# schematic_tsc.net
KiCad netlist of a schematic drawn in EAGLE
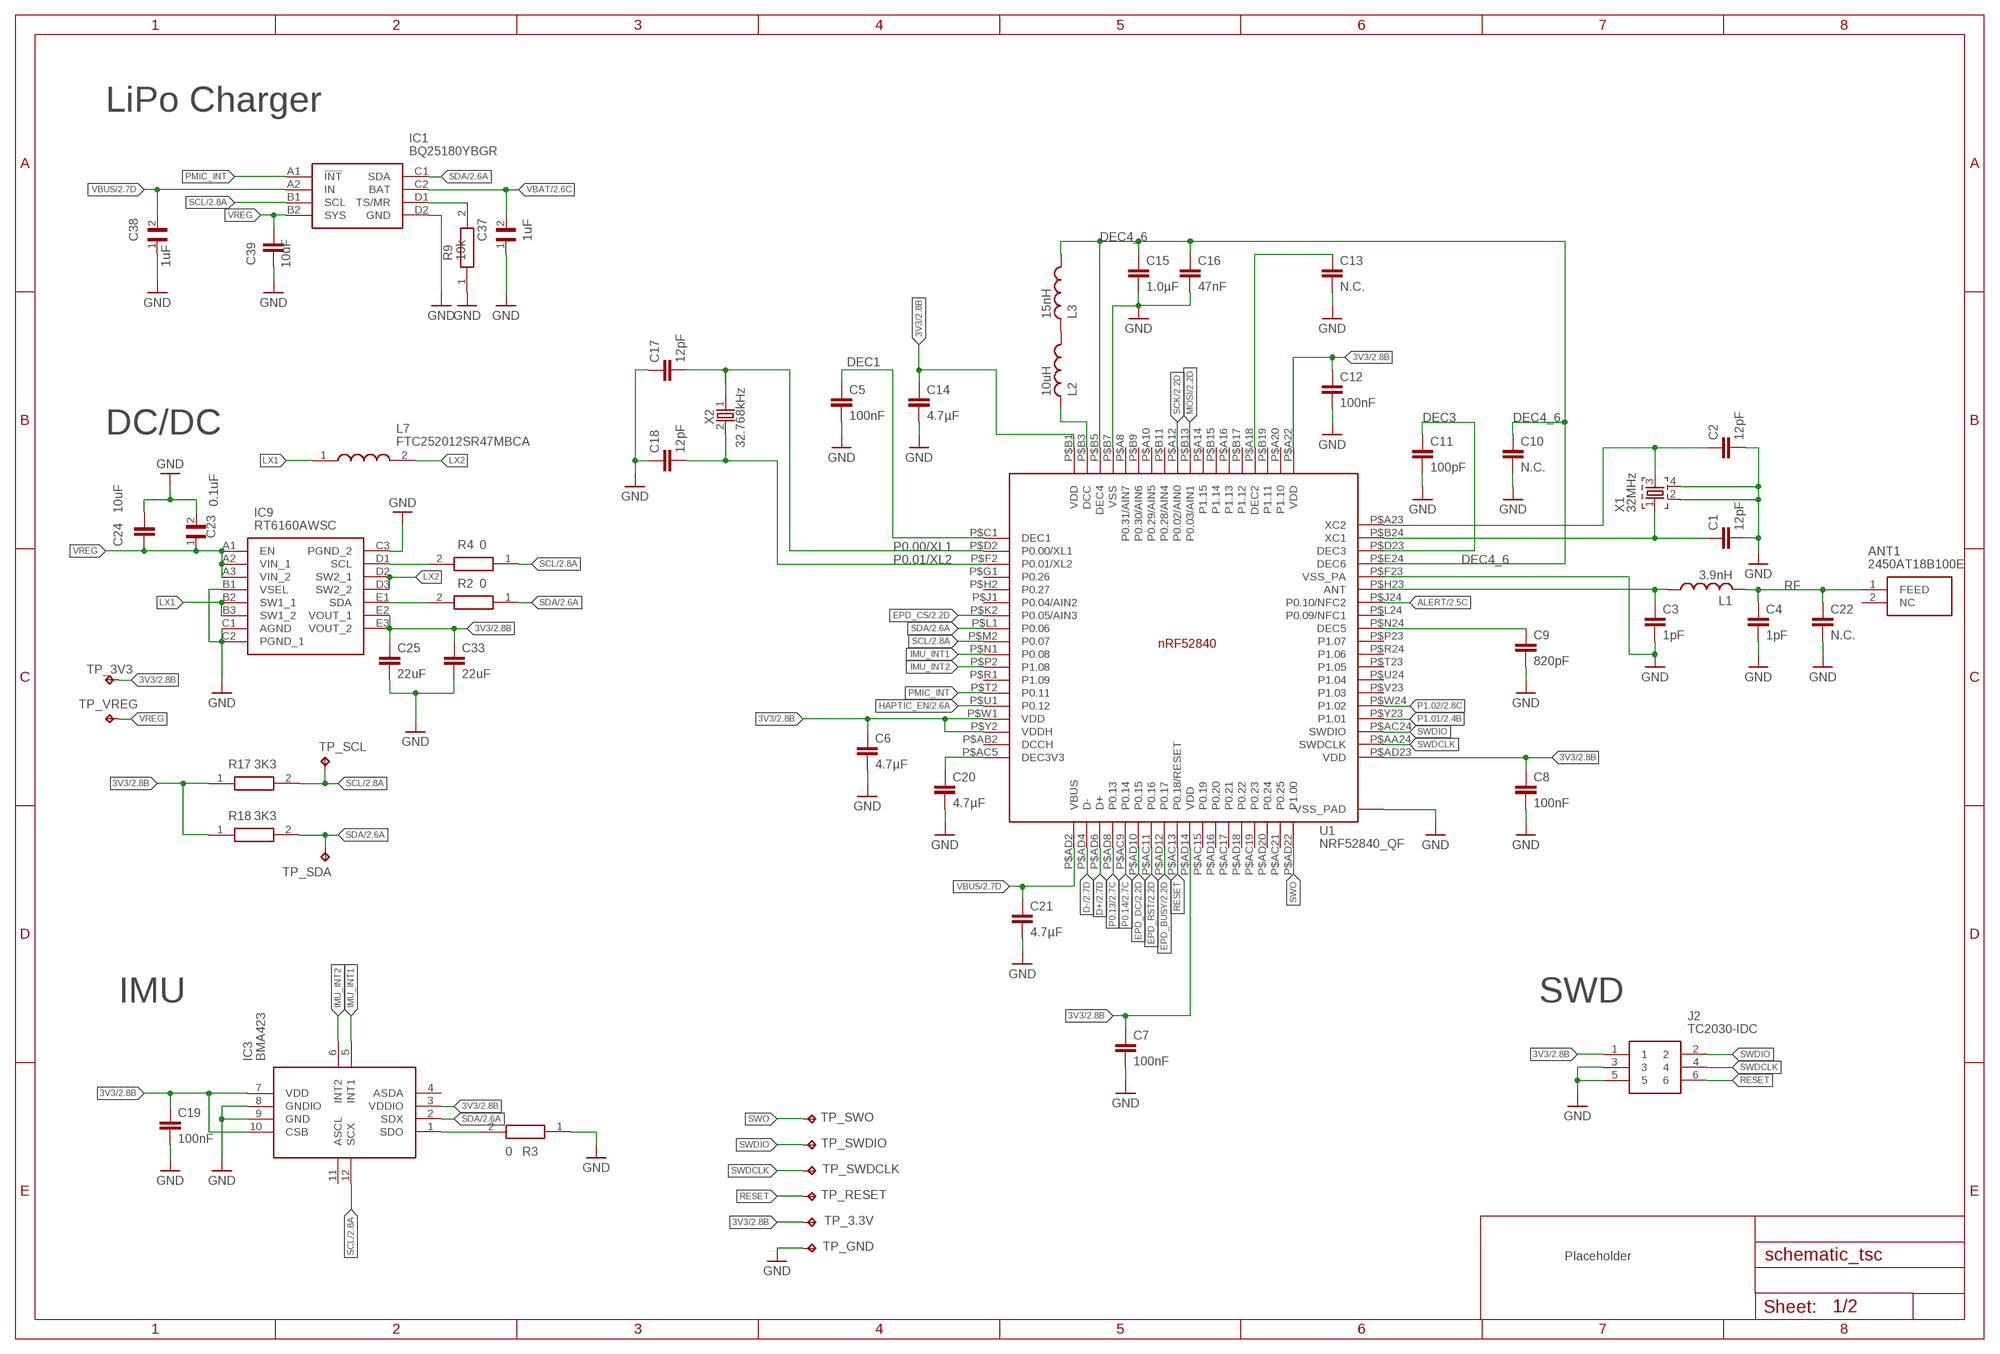
[diagram p0: schematic, sheet 1]
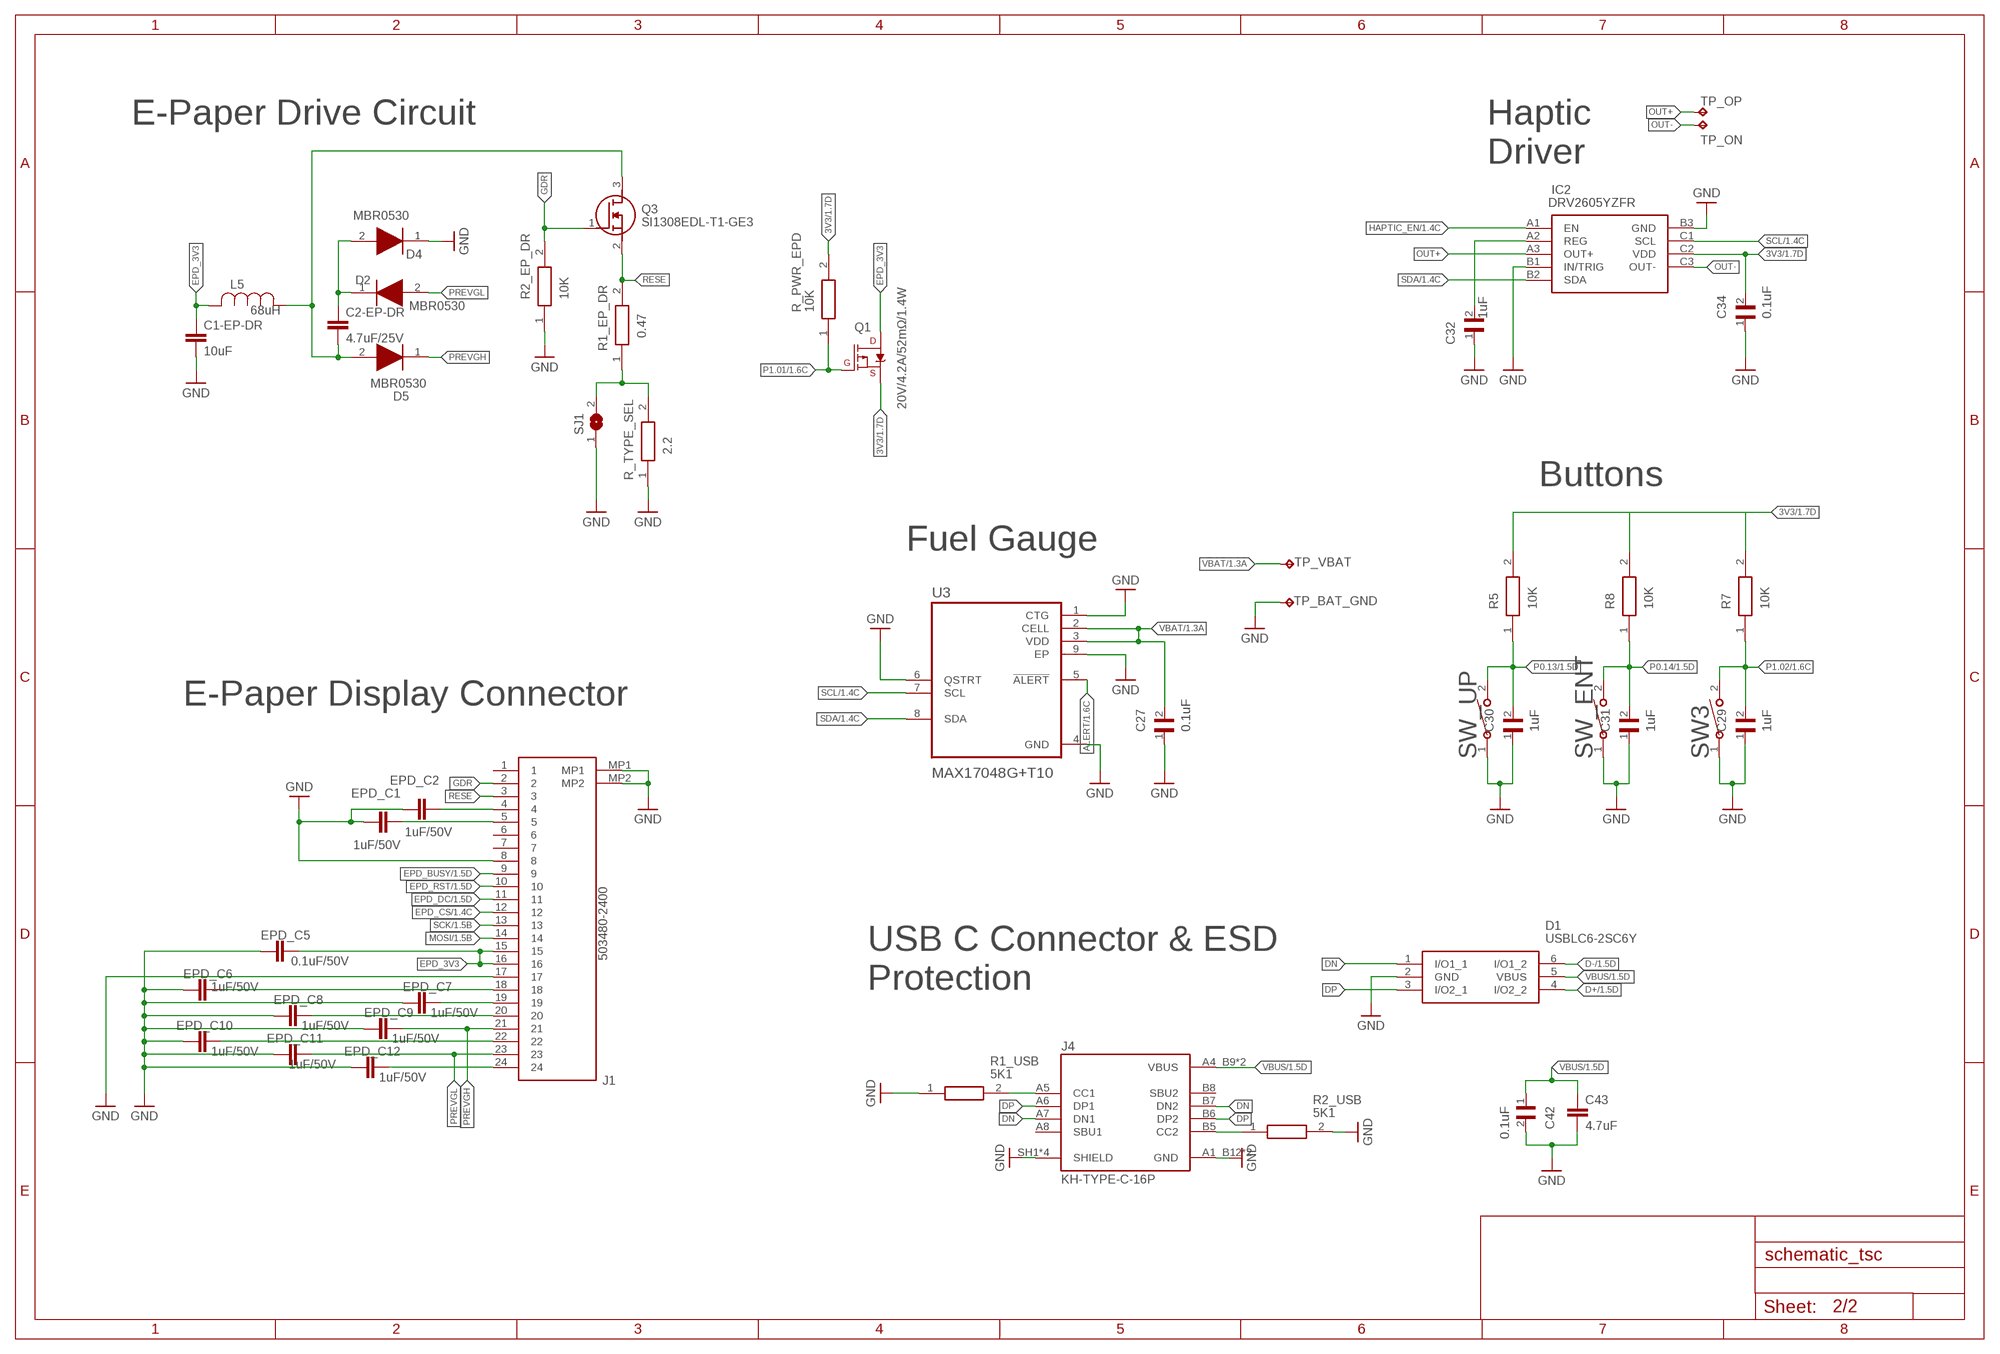
[diagram p1: schematic, sheet 2]

(export (version "E")
  (design (tool "Eeschema 10.0.6"))
  (components
    (comp (ref "ANT1")
      (value "2450AT18B100E")
      (footprint "eagle-import:2450AT18B100E_ANTC3216X140N")
      (fields (field (name "MOUSER_PART_NUMBER") "609-2450AT18B100E"))
      (libsource (lib "eagle-import") (part "2450AT18B100E_2450AT18B100E"))
    )
    (comp (ref "C1")
      (value "12pF")
      (footprint "eagle-import:NORDIC_NRF_3_RESC0201_L")
      (libsource (lib "eagle-import") (part "NORDIC_NRF_3_CAPACITOR_0201_L"))
    )
    (comp (ref "C2")
      (value "12pF")
      (footprint "eagle-import:NORDIC_NRF_3_RESC0201_L")
      (libsource (lib "eagle-import") (part "NORDIC_NRF_3_CAPACITOR_0201_L"))
    )
    (comp (ref "C3")
      (value "1pF")
      (footprint "eagle-import:NORDIC_NRF_3_RESC0201_L")
      (libsource (lib "eagle-import") (part "NORDIC_NRF_3_CAPACITOR_0201_L"))
    )
    (comp (ref "C4")
      (value "1pF")
      (footprint "eagle-import:NORDIC_NRF_3_RESC0201_L")
      (libsource (lib "eagle-import") (part "NORDIC_NRF_3_CAPACITOR_0201_L"))
    )
    (comp (ref "C5")
      (value "100nF")
      (footprint "eagle-import:NORDIC_NRF_3_RESC0201_L")
      (libsource (lib "eagle-import") (part "NORDIC_NRF_3_CAPACITOR_0201_L"))
    )
    (comp (ref "C6")
      (value "4.7µF")
      (footprint "eagle-import:NORDIC_NRF_3_RESC0402_L")
      (libsource (lib "eagle-import") (part "NORDIC_NRF_3_CAPACITOR_0402_L"))
    )
    (comp (ref "C7")
      (value "100nF")
      (footprint "eagle-import:NORDIC_NRF_3_RESC0201_L")
      (libsource (lib "eagle-import") (part "NORDIC_NRF_3_CAPACITOR_0201_L"))
    )
    (comp (ref "C8")
      (value "100nF")
      (footprint "eagle-import:NORDIC_NRF_3_RESC0201_L")
      (libsource (lib "eagle-import") (part "NORDIC_NRF_3_CAPACITOR_0201_L"))
    )
    (comp (ref "C9")
      (value "820pF")
      (footprint "eagle-import:NORDIC_NRF_3_RESC0201_L")
      (libsource (lib "eagle-import") (part "NORDIC_NRF_3_CAPACITOR_0201_L"))
    )
    (comp (ref "C10")
      (value "N.C.")
      (footprint "eagle-import:NORDIC_NRF_3_RESC0201_L")
      (libsource (lib "eagle-import") (part "NORDIC_NRF_3_CAPACITOR_0201_L"))
    )
    (comp (ref "C11")
      (value "100pF")
      (footprint "eagle-import:NORDIC_NRF_3_RESC0201_L")
      (libsource (lib "eagle-import") (part "NORDIC_NRF_3_CAPACITOR_0201_L"))
    )
    (comp (ref "C12")
      (value "100nF")
      (footprint "eagle-import:NORDIC_NRF_3_RESC0201_L")
      (libsource (lib "eagle-import") (part "NORDIC_NRF_3_CAPACITOR_0201_L"))
    )
    (comp (ref "C13")
      (value "N.C.")
      (footprint "eagle-import:NORDIC_NRF_3_RESC0201_L")
      (libsource (lib "eagle-import") (part "NORDIC_NRF_3_CAPACITOR_0201_L"))
    )
    (comp (ref "C14")
      (value "4.7µF")
      (footprint "eagle-import:NORDIC_NRF_3_RESC0402_L")
      (libsource (lib "eagle-import") (part "NORDIC_NRF_3_CAPACITOR_0402_L"))
    )
    (comp (ref "C15")
      (value "1.0µF")
      (footprint "eagle-import:NORDIC_NRF_3_RESC0402_L")
      (libsource (lib "eagle-import") (part "NORDIC_NRF_3_CAPACITOR_0402_L"))
    )
    (comp (ref "C16")
      (value "47nF")
      (footprint "eagle-import:NORDIC_NRF_3_RESC0201_L")
      (libsource (lib "eagle-import") (part "NORDIC_NRF_3_CAPACITOR_0201_L"))
    )
    (comp (ref "C17")
      (value "12pF")
      (footprint "eagle-import:NORDIC_NRF_3_RESC0201_L")
      (libsource (lib "eagle-import") (part "NORDIC_NRF_3_CAPACITOR_0201_L"))
    )
    (comp (ref "C18")
      (value "12pF")
      (footprint "eagle-import:NORDIC_NRF_3_RESC0201_L")
      (libsource (lib "eagle-import") (part "NORDIC_NRF_3_CAPACITOR_0201_L"))
    )
    (comp (ref "C19")
      (value "100nF")
      (footprint "eagle-import:NORDIC_NRF_3_RESC0201_L")
      (libsource (lib "eagle-import") (part "NORDIC_NRF_3_CAPACITOR_0201_L"))
    )
    (comp (ref "C20")
      (value "4.7µF")
      (footprint "eagle-import:NORDIC_NRF_3_RESC0402_L")
      (libsource (lib "eagle-import") (part "NORDIC_NRF_3_CAPACITOR_0402_L"))
    )
    (comp (ref "C21")
      (value "4.7µF")
      (footprint "eagle-import:NORDIC_NRF_3_RESC0402_L")
      (libsource (lib "eagle-import") (part "NORDIC_NRF_3_CAPACITOR_0402_L"))
    )
    (comp (ref "C22")
      (value "N.C.")
      (footprint "eagle-import:NORDIC_NRF_3_RESC0201_L")
      (libsource (lib "eagle-import") (part "NORDIC_NRF_3_CAPACITOR_0201_L"))
    )
    (comp (ref "C23")
      (value "0.1uF")
      (footprint "eagle-import:GRM011R60J152KE01L_2_CAPC0201X13N")
      (fields (field (name "MF") "Murata") (field (name "MP") "GRM011R60J152KE01L"))
      (libsource (lib "eagle-import") (part "GRM011R60J152KE01L_2_GRM011R60J152KE01L"))
    )
    (comp (ref "C24")
      (value "10uF")
      (footprint "eagle-import:NORDIC_NRF_3_RESC0402_L")
      (libsource (lib "eagle-import") (part "NORDIC_NRF_3_CAPACITOR_0402_L"))
    )
    (comp (ref "C25")
      (value "22uF")
      (footprint "eagle-import:NORDIC_NRF_3_RESC0402_L")
      (libsource (lib "eagle-import") (part "NORDIC_NRF_3_CAPACITOR_0402_L"))
    )
    (comp (ref "C33")
      (value "22uF")
      (footprint "eagle-import:NORDIC_NRF_3_RESC0402_L")
      (libsource (lib "eagle-import") (part "NORDIC_NRF_3_CAPACITOR_0402_L"))
    )
    (comp (ref "C37")
      (value "1uF")
      (footprint "eagle-import:GRM011R60J152KE01L_2_CAPC0201X13N")
      (fields (field (name "MF") "Murata") (field (name "MP") "GRM011R60J152KE01L"))
      (libsource (lib "eagle-import") (part "GRM011R60J152KE01L_2_GRM011R60J152KE01L"))
    )
    (comp (ref "C38")
      (value "1uF")
      (footprint "eagle-import:GRM011R60J152KE01L_2_CAPC0201X13N")
      (fields (field (name "MF") "Murata") (field (name "MP") "GRM011R60J152KE01L"))
      (libsource (lib "eagle-import") (part "GRM011R60J152KE01L_2_GRM011R60J152KE01L"))
    )
    (comp (ref "C39")
      (value "10uF")
      (footprint "eagle-import:NORDIC_NRF_3_RESC0402_L")
      (libsource (lib "eagle-import") (part "NORDIC_NRF_3_CAPACITOR_0402_L"))
    )
    (comp (ref "IC1")
      (value "BQ25180YBGR")
      (footprint "eagle-import:BQ25180YBGR_BGA8C40P2X4_100X155X50")
      (fields (field (name "MOUSER_PART_NUMBER") "595-BQ25180YBGR"))
      (libsource (lib "eagle-import") (part "BQ25180YBGR_BQ25180YBGR"))
    )
    (comp (ref "IC3")
      (value "BMA423")
      (footprint "eagle-import:BMA423_BMA423")
      (fields (field (name "MOUSER_PART_NUMBER") "262-BMA423"))
      (libsource (lib "eagle-import") (part "BMA423_BMA423"))
    )
    (comp (ref "IC9")
      (value "RT6160AWSC")
      (footprint "eagle-import:RT6160AWSC_BGA15C40P3X5_140X230X60")
      (fields (field (name "MOUSER_PART_NUMBER") "835-RT6160AWSC"))
      (libsource (lib "eagle-import") (part "RT6160AWSC_RT6160AWSC"))
    )
    (comp (ref "J2")
      (value "TC2030-IDC")
      (footprint "eagle-import:TC2030-IDC_TC2030IDC")
      (libsource (lib "eagle-import") (part "TC2030-IDC_TC2030-IDC"))
    )
    (comp (ref "L1")
      (value "3.9nH")
      (footprint "eagle-import:NORDIC_NRF_2_RESC0402_L")
      (libsource (lib "eagle-import") (part "NORDIC_NRF_2_INDUCTOR_0402_L"))
    )
    (comp (ref "L2")
      (value "10uH")
      (footprint "eagle-import:NORDIC_NRF_2_RESC0603_L")
      (libsource (lib "eagle-import") (part "NORDIC_NRF_2_INDUCTOR_0603_L"))
    )
    (comp (ref "L3")
      (value "15nH")
      (footprint "eagle-import:NORDIC_NRF_2_RESC0402_L")
      (libsource (lib "eagle-import") (part "NORDIC_NRF_2_INDUCTOR_0402_L"))
    )
    (comp (ref "L7")
      (value "FTC252012SR47MBCA")
      (footprint "eagle-import:MLP2016SR47MT0S1_INDC2016X100N")
      (libsource (lib "eagle-import") (part "MLP2016SR47MT0S1_FTC252012SR47MBCA"))
    )
    (comp (ref "R2")
      (value "0")
      (footprint "eagle-import:CPF0201D7K68C1_0201")
      (libsource (lib "eagle-import") (part "CPF0201D7K68C1_CPF0201D7K68C1"))
    )
    (comp (ref "R3")
      (value "0")
      (footprint "eagle-import:ERA-1AEB3401C_0201")
      (libsource (lib "eagle-import") (part "ERA-1AEB3401C_CPF0201D7K68C1"))
    )
    (comp (ref "R4")
      (value "0")
      (footprint "eagle-import:CPF0201D7K68C1_0201")
      (libsource (lib "eagle-import") (part "CPF0201D7K68C1_CPF0201D7K68C1"))
    )
    (comp (ref "R9")
      (value "10k")
      (footprint "eagle-import:CPF0201D7K68C1_0201")
      (libsource (lib "eagle-import") (part "CPF0201D7K68C1_CPF0201D7K68C1"))
    )
    (comp (ref "R17")
      (value "3K3")
      (footprint "eagle-import:ERA-1AEB3401C_0201")
      (libsource (lib "eagle-import") (part "ERA-1AEB3401C_CPF0201D7K68C1"))
    )
    (comp (ref "R18")
      (value "3K3")
      (footprint "eagle-import:ERA-1AEB3401C_0201")
      (libsource (lib "eagle-import") (part "ERA-1AEB3401C_CPF0201D7K68C1"))
    )
    (comp (ref "TP_3.3V")
      (value "HECTOR_WATCH_1_TPTP20R")
      (footprint "eagle-import:HECTOR_WATCH_1_TP20R")
      (libsource (lib "eagle-import") (part "HECTOR_WATCH_1_TPTP20R"))
    )
    (comp (ref "TP_3V3")
      (value "HECTOR_WATCH_1_TPTP20R")
      (footprint "eagle-import:HECTOR_WATCH_1_TP20R")
      (libsource (lib "eagle-import") (part "HECTOR_WATCH_1_TPTP20R"))
    )
    (comp (ref "TP_GND")
      (value "HECTOR_WATCH_1_TPTP20R")
      (footprint "eagle-import:HECTOR_WATCH_1_TP20R")
      (libsource (lib "eagle-import") (part "HECTOR_WATCH_1_TPTP20R"))
    )
    (comp (ref "TP_RESET")
      (value "HECTOR_WATCH_1_TPTP20R")
      (footprint "eagle-import:HECTOR_WATCH_1_TP20R")
      (libsource (lib "eagle-import") (part "HECTOR_WATCH_1_TPTP20R"))
    )
    (comp (ref "TP_SCL")
      (value "HECTOR_WATCH_1_TPTP20R")
      (footprint "eagle-import:HECTOR_WATCH_1_TP20R")
      (libsource (lib "eagle-import") (part "HECTOR_WATCH_1_TPTP20R"))
    )
    (comp (ref "TP_SDA")
      (value "HECTOR_WATCH_1_TPTP20R")
      (footprint "eagle-import:HECTOR_WATCH_1_TP20R")
      (libsource (lib "eagle-import") (part "HECTOR_WATCH_1_TPTP20R"))
    )
    (comp (ref "TP_SWDCLK")
      (value "HECTOR_WATCH_1_TPTP20R")
      (footprint "eagle-import:HECTOR_WATCH_1_TP20R")
      (libsource (lib "eagle-import") (part "HECTOR_WATCH_1_TPTP20R"))
    )
    (comp (ref "TP_SWDIO")
      (value "HECTOR_WATCH_1_TPTP20R")
      (footprint "eagle-import:HECTOR_WATCH_1_TP20R")
      (libsource (lib "eagle-import") (part "HECTOR_WATCH_1_TPTP20R"))
    )
    (comp (ref "TP_SWO")
      (value "HECTOR_WATCH_1_TPTP20R")
      (footprint "eagle-import:HECTOR_WATCH_1_TP20R")
      (libsource (lib "eagle-import") (part "HECTOR_WATCH_1_TPTP20R"))
    )
    (comp (ref "TP_VREG")
      (value "HECTOR_WATCH_1_TPTP20R")
      (footprint "eagle-import:HECTOR_WATCH_1_TP20R")
      (libsource (lib "eagle-import") (part "HECTOR_WATCH_1_TPTP20R"))
    )
    (comp (ref "U1")
      (value "NRF52840_QF")
      (footprint "eagle-import:NORDIC_NRF_4_AQFN50P700X700X85_HS-74N")
      (libsource (lib "eagle-import") (part "NORDIC_NRF_4_NRF52840_QF"))
    )
    (comp (ref "X1")
      (value "32MHz")
      (footprint "eagle-import:NORDIC_NRF_BT-XTAL_2016_N")
      (libsource (lib "eagle-import") (part "NORDIC_NRF_XTAL_32MHZ"))
    )
    (comp (ref "X2")
      (value "32.768kHz")
      (footprint "eagle-import:NORDIC_NRF_1_XTAL_3215_N")
      (libsource (lib "eagle-import") (part "NORDIC_NRF_1_XTAL_32KHZ"))
    )
    (comp (ref "C1-EP-DR")
      (value "10uF")
      (footprint "eagle-import:NORDIC_NRF_3_RESC0402_L")
      (libsource (lib "eagle-import") (part "NORDIC_NRF_3_CAPACITOR_0402_L"))
    )
    (comp (ref "C2-EP-DR")
      (value "4.7uF/25V")
      (footprint "eagle-import:NORDIC_NRF_3_RESC0402_L")
      (libsource (lib "eagle-import") (part "NORDIC_NRF_3_CAPACITOR_0402_L"))
    )
    (comp (ref "C27")
      (value "0.1uF")
      (footprint "eagle-import:GRM011R60J152KE01L_2_CAPC0201X13N")
      (fields (field (name "MF") "Murata") (field (name "MP") "GRM011R60J152KE01L"))
      (libsource (lib "eagle-import") (part "GRM011R60J152KE01L_2_GRM011R60J152KE01L"))
    )
    (comp (ref "C29")
      (value "1uF")
      (footprint "eagle-import:GRM011R60J152KE01L_2_CAPC0201X13N")
      (fields (field (name "MF") "Murata") (field (name "MP") "GRM011R60J152KE01L"))
      (libsource (lib "eagle-import") (part "GRM011R60J152KE01L_2_GRM011R60J152KE01L"))
    )
    (comp (ref "C30")
      (value "1uF")
      (footprint "eagle-import:GRM011R60J152KE01L_2_CAPC0201X13N")
      (fields (field (name "MF") "Murata") (field (name "MP") "GRM011R60J152KE01L"))
      (libsource (lib "eagle-import") (part "GRM011R60J152KE01L_2_GRM011R60J152KE01L"))
    )
    (comp (ref "C31")
      (value "1uF")
      (footprint "eagle-import:GRM011R60J152KE01L_2_CAPC0201X13N")
      (fields (field (name "MF") "Murata") (field (name "MP") "GRM011R60J152KE01L"))
      (libsource (lib "eagle-import") (part "GRM011R60J152KE01L_2_GRM011R60J152KE01L"))
    )
    (comp (ref "C32")
      (value "1uF")
      (footprint "eagle-import:GRM011R60J152KE01L_2_CAPC0201X13N")
      (fields (field (name "MF") "Murata") (field (name "MP") "GRM011R60J152KE01L"))
      (libsource (lib "eagle-import") (part "GRM011R60J152KE01L_2_GRM011R60J152KE01L"))
    )
    (comp (ref "C34")
      (value "0.1uF")
      (footprint "eagle-import:GRM011R60J152KE01L_2_CAPC0201X13N")
      (fields (field (name "MF") "Murata") (field (name "MP") "GRM011R60J152KE01L"))
      (libsource (lib "eagle-import") (part "GRM011R60J152KE01L_2_GRM011R60J152KE01L"))
    )
    (comp (ref "C42")
      (value "0.1uF")
      (footprint "eagle-import:GRM011R60J152KE01L_2_CAPC0201X13N")
      (fields (field (name "MF") "Murata") (field (name "MP") "GRM011R60J152KE01L"))
      (libsource (lib "eagle-import") (part "GRM011R60J152KE01L_2_GRM011R60J152KE01L"))
    )
    (comp (ref "C43")
      (value "4.7uF")
      (footprint "eagle-import:NORDIC_NRF_3_RESC0402_L")
      (libsource (lib "eagle-import") (part "NORDIC_NRF_3_CAPACITOR_0402_L"))
    )
    (comp (ref "D1")
      (value "USBLC6-2SC6Y")
      (footprint "eagle-import:ESP32_C6_LIBRARY_3_SOT95P280X145-6N")
      (fields (field (name "MF") "STMicroelectronics"))
      (libsource (lib "eagle-import") (part "ESP32_C6_LIBRARY_3_USBLC6-2SC6Y"))
    )
    (comp (ref "D2")
      (value "MBR0530")
      (footprint "eagle-import:ESP32_C6_LIBRARY_5_SOD3716X135N")
      (fields (field (name "MF") "ON Semiconductor"))
      (libsource (lib "eagle-import") (part "ESP32_C6_LIBRARY_5_MBR0530"))
    )
    (comp (ref "D4")
      (value "MBR0530")
      (footprint "eagle-import:ESP32_C6_LIBRARY_5_SOD3716X135N")
      (fields (field (name "MF") "ON Semiconductor"))
      (libsource (lib "eagle-import") (part "ESP32_C6_LIBRARY_5_MBR0530"))
    )
    (comp (ref "D5")
      (value "MBR0530")
      (footprint "eagle-import:ESP32_C6_LIBRARY_5_SOD3716X135N")
      (fields (field (name "MF") "ON Semiconductor"))
      (libsource (lib "eagle-import") (part "ESP32_C6_LIBRARY_5_MBR0530"))
    )
    (comp (ref "EPD_C1")
      (value "1uF/50V")
      (footprint "eagle-import:NORDIC_NRF_3_RESC0201_L")
      (libsource (lib "eagle-import") (part "NORDIC_NRF_3_CAPACITOR_0201_L"))
    )
    (comp (ref "EPD_C2")
      (value "1uF/50V")
      (footprint "eagle-import:NORDIC_NRF_3_RESC0201_L")
      (libsource (lib "eagle-import") (part "NORDIC_NRF_3_CAPACITOR_0201_L"))
    )
    (comp (ref "EPD_C5")
      (value "0.1uF/50V")
      (footprint "eagle-import:NORDIC_NRF_3_RESC0201_L")
      (libsource (lib "eagle-import") (part "NORDIC_NRF_3_CAPACITOR_0201_L"))
    )
    (comp (ref "EPD_C6")
      (value "1uF/50V")
      (footprint "eagle-import:NORDIC_NRF_3_RESC0402_L")
      (libsource (lib "eagle-import") (part "NORDIC_NRF_3_CAPACITOR_0402_L"))
    )
    (comp (ref "EPD_C7")
      (value "1uF/50V")
      (footprint "eagle-import:NORDIC_NRF_3_RESC0402_L")
      (libsource (lib "eagle-import") (part "NORDIC_NRF_3_CAPACITOR_0402_L"))
    )
    (comp (ref "EPD_C8")
      (value "1uF/50V")
      (footprint "eagle-import:NORDIC_NRF_3_RESC0402_L")
      (libsource (lib "eagle-import") (part "NORDIC_NRF_3_CAPACITOR_0402_L"))
    )
    (comp (ref "EPD_C9")
      (value "1uF/50V")
      (footprint "eagle-import:NORDIC_NRF_3_RESC0402_L")
      (libsource (lib "eagle-import") (part "NORDIC_NRF_3_CAPACITOR_0402_L"))
    )
    (comp (ref "EPD_C10")
      (value "1uF/50V")
      (footprint "eagle-import:NORDIC_NRF_3_RESC0402_L")
      (libsource (lib "eagle-import") (part "NORDIC_NRF_3_CAPACITOR_0402_L"))
    )
    (comp (ref "EPD_C11")
      (value "1uF/50V")
      (footprint "eagle-import:NORDIC_NRF_3_RESC0402_L")
      (libsource (lib "eagle-import") (part "NORDIC_NRF_3_CAPACITOR_0402_L"))
    )
    (comp (ref "EPD_C12")
      (value "1uF/50V")
      (footprint "eagle-import:NORDIC_NRF_3_RESC0402_L")
      (libsource (lib "eagle-import") (part "NORDIC_NRF_3_CAPACITOR_0402_L"))
    )
    (comp (ref "IC2")
      (value "DRV2605YZFR")
      (footprint "eagle-import:DRV2605YZFR_BGA9C50P3X3_144X144X62")
      (libsource (lib "eagle-import") (part "DRV2605YZFR_DRV2605YZFR"))
    )
    (comp (ref "J1")
      (value "503480-2400")
      (footprint "eagle-import:503480-2400_5034802400")
      (fields (field (name "MOUSER_PART_NUMBER") "538-503480-2400"))
      (libsource (lib "eagle-import") (part "503480-2400_503480-2400"))
    )
    (comp (ref "J4")
      (value "KH-TYPE-C-16P")
      (footprint "eagle-import:KH-TYPE-C-16P_KINGHELM_KH-TYPE-C-16P")
      (fields (field (name "MF") "kinghelm"))
      (libsource (lib "eagle-import") (part "KH-TYPE-C-16P_KH-TYPE-C-16P"))
    )
    (comp (ref "L5")
      (value "68uH")
      (footprint "eagle-import:ESP32_C6_LIBRARY_2_IND_4828-WE-TPC_WRE")
      (fields
        (field (name "MANUFACTURER_PART_NUMBER") "744043680")
        (field (name "COPYRIGHT") "Copyright (C) 2024 Ultra Librarian. All rights reserved.")
      )
      (libsource (lib "eagle-import") (part "ESP32_C6_LIBRARY_2_744043680IND_4828-WE-TPC_WRE"))
    )
    (comp (ref "Q1")
      (value "20V/4.2A/52mΩ/1.4W")
      (footprint "eagle-import:ESP32_C6_LIBRARY_4_ESP32_C6_LIBRARY_4_ESP32_C6_LIBRARY_4_ESP32_C6_LIBRARY_4_ESP32_WROVER_SPARKFUN-DISCRETESEMI_SOT23-3")
      (libsource (lib "eagle-import") (part "ESP32_C6_LIBRARY_4_ESP32_WROVER_SPARKFUN-DISCRETESEMI_MOSFET_PCH-DMG2305UX-7"))
    )
    (comp (ref "Q3")
      (value "SI1308EDL-T1-GE3")
      (footprint "eagle-import:ESP32_C6_LIBRARY_6_SOT65P210X110-3N")
      (fields (field (name "MF") "Vishay Siliconix"))
      (libsource (lib "eagle-import") (part "ESP32_C6_LIBRARY_6_SI1308EDL-T1-GE3"))
    )
    (comp (ref "R1_EP_DR")
      (value "0.47")
      (footprint "eagle-import:CPF0201D7K68C1_0201")
      (libsource (lib "eagle-import") (part "CPF0201D7K68C1_CPF0201D7K68C1"))
    )
    (comp (ref "R1_USB")
      (value "5K1")
      (footprint "eagle-import:ERA-1AEB3401C_0201")
      (libsource (lib "eagle-import") (part "ERA-1AEB3401C_CPF0201D7K68C1"))
    )
    (comp (ref "R2_EP_DR")
      (value "10K")
      (footprint "eagle-import:CPF0201D7K68C1_0201")
      (libsource (lib "eagle-import") (part "CPF0201D7K68C1_CPF0201D7K68C1"))
    )
    (comp (ref "R2_USB")
      (value "5K1")
      (footprint "eagle-import:ERA-1AEB3401C_0201")
      (libsource (lib "eagle-import") (part "ERA-1AEB3401C_CPF0201D7K68C1"))
    )
    (comp (ref "R5")
      (value "10K")
      (footprint "eagle-import:CPF0201D7K68C1_0201")
      (libsource (lib "eagle-import") (part "CPF0201D7K68C1_CPF0201D7K68C1"))
    )
    (comp (ref "R7")
      (value "10K")
      (footprint "eagle-import:CPF0201D7K68C1_0201")
      (libsource (lib "eagle-import") (part "CPF0201D7K68C1_CPF0201D7K68C1"))
    )
    (comp (ref "R8")
      (value "10K")
      (footprint "eagle-import:CPF0201D7K68C1_0201")
      (libsource (lib "eagle-import") (part "CPF0201D7K68C1_CPF0201D7K68C1"))
    )
    (comp (ref "R_PWR_EPD")
      (value "10K")
      (footprint "eagle-import:CPF0201D7K68C1_0201")
      (libsource (lib "eagle-import") (part "CPF0201D7K68C1_CPF0201D7K68C1"))
    )
    (comp (ref "R_TYPE_SEL")
      (value "2.2")
      (footprint "eagle-import:CPF0201D7K68C1_0201")
      (libsource (lib "eagle-import") (part "CPF0201D7K68C1_CPF0201D7K68C1"))
    )
    (comp (ref "SJ1")
      (value "ESP32_C6_LIBRARY_7_JUMPER_SJ")
      (footprint "eagle-import:ESP32_C6_LIBRARY_7_JUMPER_SJ")
      (libsource (lib "eagle-import") (part "ESP32_C6_LIBRARY_7_JUMPER_SJ"))
    )
    (comp (ref "SW3")
      (value "2025-10-22_07-23-44_LIBRARY_EVP-AKE31ASW_EVP-AKE31A_PAN")
      (footprint "eagle-import:2025-10-22_07-23-44_LIBRARY_SW_EVP-AKE31A_PAN")
      (fields
        (field (name "MANUFACTURER_PART_NUMBER") "EVP-AKE31A")
        (field (name "COPYRIGHT") "Copyright (C) 2025 Ultra Librarian. All rights reserved.")
      )
      (libsource (lib "eagle-import") (part "2025-10-22_07-23-44_LIBRARY_EVP-AKE31ASW_EVP-AKE31A_PAN"))
    )
    (comp (ref "SW_ENT")
      (value "2025-10-22_07-23-44_LIBRARY_EVP-AKE31ASW_EVP-AKE31A_PAN")
      (footprint "eagle-import:2025-10-22_07-23-44_LIBRARY_SW_EVP-AKE31A_PAN")
      (fields
        (field (name "MANUFACTURER_PART_NUMBER") "EVP-AKE31A")
        (field (name "COPYRIGHT") "Copyright (C) 2025 Ultra Librarian. All rights reserved.")
      )
      (libsource (lib "eagle-import") (part "2025-10-22_07-23-44_LIBRARY_EVP-AKE31ASW_EVP-AKE31A_PAN"))
    )
    (comp (ref "SW_UP")
      (value "2025-10-22_07-23-44_LIBRARY_EVP-AKE31ASW_EVP-AKE31A_PAN")
      (footprint "eagle-import:2025-10-22_07-23-44_LIBRARY_SW_EVP-AKE31A_PAN")
      (fields
        (field (name "MANUFACTURER_PART_NUMBER") "EVP-AKE31A")
        (field (name "COPYRIGHT") "Copyright (C) 2025 Ultra Librarian. All rights reserved.")
      )
      (libsource (lib "eagle-import") (part "2025-10-22_07-23-44_LIBRARY_EVP-AKE31ASW_EVP-AKE31A_PAN"))
    )
    (comp (ref "TP_BAT_GND")
      (value "HECTOR_WATCH_1_TPTP20R")
      (footprint "eagle-import:HECTOR_WATCH_1_TP20R")
      (libsource (lib "eagle-import") (part "HECTOR_WATCH_1_TPTP20R"))
    )
    (comp (ref "TP_ON")
      (value "HECTOR_WATCH_1_TPTP20R")
      (footprint "eagle-import:HECTOR_WATCH_1_TP20R")
      (libsource (lib "eagle-import") (part "HECTOR_WATCH_1_TPTP20R"))
    )
    (comp (ref "TP_OP")
      (value "HECTOR_WATCH_1_TPTP20R")
      (footprint "eagle-import:HECTOR_WATCH_1_TP20R")
      (libsource (lib "eagle-import") (part "HECTOR_WATCH_1_TPTP20R"))
    )
    (comp (ref "TP_VBAT")
      (value "HECTOR_WATCH_1_TPTP20R")
      (footprint "eagle-import:HECTOR_WATCH_1_TP20R")
      (libsource (lib "eagle-import") (part "HECTOR_WATCH_1_TPTP20R"))
    )
    (comp (ref "U3")
      (value "MAX17048G+T10")
      (footprint "eagle-import:ESP32_C6_LIBRARY_SON50P200X200X80-9N")
      (fields (field (name "MF") "Analog Devices"))
      (libsource (lib "eagle-import") (part "ESP32_C6_LIBRARY_MAX17048G+T10"))
    )
  )
  (nets
    (net (code "1") (name "3V3") (class "Default")
      (node (ref "C12") (pin "1") (pinfunction "1_1") (pintype "passive"))
      (node (ref "C14") (pin "1") (pinfunction "1_1") (pintype "passive"))
      (node (ref "C19") (pin "1") (pinfunction "1_1") (pintype "passive"))
      (node (ref "C25") (pin "1") (pinfunction "1_1") (pintype "passive"))
      (node (ref "C33") (pin "1") (pinfunction "1_1") (pintype "passive"))
      (node (ref "C34") (pin "2") (pinfunction "2_2") (pintype "passive"))
      (node (ref "C6") (pin "1") (pinfunction "1_1") (pintype "passive"))
      (node (ref "C7") (pin "1") (pinfunction "1_1") (pintype "passive"))
      (node (ref "C8") (pin "1") (pinfunction "1_1") (pintype "passive"))
      (node (ref "IC2") (pin "C2") (pinfunction "VDD_C2") (pintype "bidirectional"))
      (node (ref "IC3") (pin "10") (pinfunction "CSB_10") (pintype "bidirectional"))
      (node (ref "IC3") (pin "3") (pinfunction "VDDIO_3") (pintype "bidirectional"))
      (node (ref "IC3") (pin "7") (pinfunction "VDD_7") (pintype "bidirectional"))
      (node (ref "IC9") (pin "E2") (pinfunction "VOUT_1_E2") (pintype "bidirectional"))
      (node (ref "IC9") (pin "E3") (pinfunction "VOUT_2_E3") (pintype "bidirectional"))
      (node (ref "J2") (pin "1") (pinfunction "1_1") (pintype "bidirectional"))
      (node (ref "Q1") (pin "2") (pinfunction "S_2") (pintype "bidirectional"))
      (node (ref "R17") (pin "1") (pinfunction "1_1") (pintype "bidirectional"))
      (node (ref "R18") (pin "1") (pinfunction "1_1") (pintype "bidirectional"))
      (node (ref "R5") (pin "2") (pinfunction "2_2") (pintype "bidirectional"))
      (node (ref "R_PWR_EPD") (pin "2") (pinfunction "2_2") (pintype "bidirectional"))
      (node (ref "TP_3.3V") (pin "TP") (pinfunction "TP_TP") (pintype "input"))
      (node (ref "TP_3V3") (pin "TP") (pinfunction "TP_TP") (pintype "input"))
      (node (ref "U1") (pin "P$A22") (pinfunction "VDD_P$A22") (pintype "power_in"))
      (node (ref "U1") (pin "P$AD14") (pinfunction "VDD_P$AD14") (pintype "power_in"))
      (node (ref "U1") (pin "P$AD23") (pinfunction "VDD_P$AD23") (pintype "power_in"))
      (node (ref "U1") (pin "P$B1") (pinfunction "VDD_P$B1") (pintype "power_in"))
      (node (ref "U1") (pin "P$W1") (pinfunction "VDD_P$W1") (pintype "power_in"))
      (node (ref "U1") (pin "P$Y2") (pinfunction "VDDH_P$Y2") (pintype "power_in"))
    )
    (net (code "2") (name "ALERT") (class "Default")
      (node (ref "U1") (pin "P$J24") (pinfunction "P0.10/NFC2_P$J24") (pintype "bidirectional"))
      (node (ref "U3") (pin "5") (pinfunction "~{ALERT}_5") (pintype "output"))
    )
    (net (code "3") (name "D+") (class "Default")
      (node (ref "D1") (pin "4") (pinfunction "I/O2_2_4") (pintype "bidirectional"))
      (node (ref "U1") (pin "P$AD6") (pinfunction "D+_P$AD6") (pintype "bidirectional"))
    )
    (net (code "4") (name "D-") (class "Default")
      (node (ref "D1") (pin "6") (pinfunction "I/O1_2_6") (pintype "bidirectional"))
      (node (ref "U1") (pin "P$AD4") (pinfunction "D-_P$AD4") (pintype "bidirectional"))
    )
    (net (code "5") (name "DEC1") (class "Default")
      (node (ref "C5") (pin "1") (pinfunction "1_1") (pintype "passive"))
      (node (ref "U1") (pin "P$C1") (pinfunction "DEC1_P$C1") (pintype "power_in"))
    )
    (net (code "6") (name "DEC3") (class "Default")
      (node (ref "C11") (pin "1") (pinfunction "1_1") (pintype "passive"))
      (node (ref "U1") (pin "P$D23") (pinfunction "DEC3_P$D23") (pintype "bidirectional"))
    )
    (net (code "7") (name "DEC4_6") (class "Default")
      (node (ref "C10") (pin "1") (pinfunction "1_1") (pintype "passive"))
      (node (ref "C15") (pin "1") (pinfunction "1_1") (pintype "passive"))
      (node (ref "C16") (pin "1") (pinfunction "1_1") (pintype "passive"))
      (node (ref "L3") (pin "1") (pinfunction "1_1") (pintype "passive"))
      (node (ref "U1") (pin "P$B5") (pinfunction "DEC4_P$B5") (pintype "power_in"))
      (node (ref "U1") (pin "P$E24") (pinfunction "DEC6_P$E24") (pintype "bidirectional"))
    )
    (net (code "8") (name "DN") (class "Default")
      (node (ref "D1") (pin "1") (pinfunction "I/O1_1_1") (pintype "bidirectional"))
      (node (ref "J4") (pin "A7") (pinfunction "DN1_A7") (pintype "bidirectional"))
      (node (ref "J4") (pin "B7") (pinfunction "DN2_B7") (pintype "bidirectional"))
    )
    (net (code "9") (name "DP") (class "Default")
      (node (ref "D1") (pin "3") (pinfunction "I/O2_1_3") (pintype "bidirectional"))
      (node (ref "J4") (pin "A6") (pinfunction "DP1_A6") (pintype "bidirectional"))
      (node (ref "J4") (pin "B6") (pinfunction "DP2_B6") (pintype "bidirectional"))
    )
    (net (code "10") (name "EPD_3V3") (class "Default")
      (node (ref "C1-EP-DR") (pin "1") (pinfunction "1_1") (pintype "passive"))
      (node (ref "EPD_C5") (pin "2") (pinfunction "2_2") (pintype "passive"))
      (node (ref "J1") (pin "15") (pinfunction "15_15") (pintype "bidirectional"))
      (node (ref "J1") (pin "16") (pinfunction "16_16") (pintype "bidirectional"))
      (node (ref "L5") (pin "2") (pinfunction "2_2") (pintype "passive"))
      (node (ref "Q1") (pin "3") (pinfunction "D_3") (pintype "bidirectional"))
    )
    (net (code "11") (name "EPD_BUSY") (class "Default")
      (node (ref "J1") (pin "9") (pinfunction "9_9") (pintype "bidirectional"))
      (node (ref "U1") (pin "P$AD12") (pinfunction "P0.17_P$AD12") (pintype "bidirectional"))
    )
    (net (code "12") (name "EPD_CS") (class "Default")
      (node (ref "J1") (pin "12") (pinfunction "12_12") (pintype "bidirectional"))
      (node (ref "U1") (pin "P$K2") (pinfunction "P0.05/AIN3_P$K2") (pintype "bidirectional"))
    )
    (net (code "13") (name "EPD_DC") (class "Default")
      (node (ref "J1") (pin "11") (pinfunction "11_11") (pintype "bidirectional"))
      (node (ref "U1") (pin "P$AD10") (pinfunction "P0.15_P$AD10") (pintype "bidirectional"))
    )
    (net (code "14") (name "EPD_RST") (class "Default")
      (node (ref "J1") (pin "10") (pinfunction "10_10") (pintype "bidirectional"))
      (node (ref "U1") (pin "P$AC11") (pinfunction "P0.16_P$AC11") (pintype "bidirectional"))
    )
    (net (code "15") (name "GDR") (class "Default")
      (node (ref "J1") (pin "2") (pinfunction "2_2") (pintype "bidirectional"))
      (node (ref "Q3") (pin "1") (pinfunction "G_1") (pintype "bidirectional"))
      (node (ref "R2_EP_DR") (pin "2") (pinfunction "2_2") (pintype "bidirectional"))
    )
    (net (code "16") (name "GND") (class "Default")
      (node (ref "C1") (pin "2") (pinfunction "2_2") (pintype "passive"))
      (node (ref "C1-EP-DR") (pin "2") (pinfunction "2_2") (pintype "passive"))
      (node (ref "C10") (pin "2") (pinfunction "2_2") (pintype "passive"))
      (node (ref "C11") (pin "2") (pinfunction "2_2") (pintype "passive"))
      (node (ref "C12") (pin "2") (pinfunction "2_2") (pintype "passive"))
      (node (ref "C13") (pin "2") (pinfunction "2_2") (pintype "passive"))
      (node (ref "C14") (pin "2") (pinfunction "2_2") (pintype "passive"))
      (node (ref "C15") (pin "2") (pinfunction "2_2") (pintype "passive"))
      (node (ref "C16") (pin "2") (pinfunction "2_2") (pintype "passive"))
      (node (ref "C17") (pin "1") (pinfunction "1_1") (pintype "passive"))
      (node (ref "C18") (pin "1") (pinfunction "1_1") (pintype "passive"))
      (node (ref "C19") (pin "2") (pinfunction "2_2") (pintype "passive"))
      (node (ref "C2") (pin "2") (pinfunction "2_2") (pintype "passive"))
      (node (ref "C20") (pin "2") (pinfunction "2_2") (pintype "passive"))
      (node (ref "C21") (pin "2") (pinfunction "2_2") (pintype "passive"))
      (node (ref "C22") (pin "2") (pinfunction "2_2") (pintype "passive"))
      (node (ref "C23") (pin "2") (pinfunction "2_2") (pintype "passive"))
      (node (ref "C24") (pin "1") (pinfunction "1_1") (pintype "passive"))
      (node (ref "C25") (pin "2") (pinfunction "2_2") (pintype "passive"))
      (node (ref "C27") (pin "1") (pinfunction "1_1") (pintype "passive"))
      (node (ref "C29") (pin "1") (pinfunction "1_1") (pintype "passive"))
      (node (ref "C3") (pin "2") (pinfunction "2_2") (pintype "passive"))
      (node (ref "C30") (pin "1") (pinfunction "1_1") (pintype "passive"))
      (node (ref "C31") (pin "1") (pinfunction "1_1") (pintype "passive"))
      (node (ref "C32") (pin "1") (pinfunction "1_1") (pintype "passive"))
      (node (ref "C33") (pin "2") (pinfunction "2_2") (pintype "passive"))
      (node (ref "C34") (pin "1") (pinfunction "1_1") (pintype "passive"))
      (node (ref "C37") (pin "1") (pinfunction "1_1") (pintype "passive"))
      (node (ref "C38") (pin "1") (pinfunction "1_1") (pintype "passive"))
      (node (ref "C39") (pin "2") (pinfunction "2_2") (pintype "passive"))
      (node (ref "C4") (pin "2") (pinfunction "2_2") (pintype "passive"))
      (node (ref "C42") (pin "2") (pinfunction "2_2") (pintype "passive"))
      (node (ref "C43") (pin "2") (pinfunction "2_2") (pintype "passive"))
      (node (ref "C5") (pin "2") (pinfunction "2_2") (pintype "passive"))
      (node (ref "C6") (pin "2") (pinfunction "2_2") (pintype "passive"))
      (node (ref "C7") (pin "2") (pinfunction "2_2") (pintype "passive"))
      (node (ref "C8") (pin "2") (pinfunction "2_2") (pintype "passive"))
      (node (ref "C9") (pin "2") (pinfunction "2_2") (pintype "passive"))
      (node (ref "D1") (pin "2") (pinfunction "GND_2") (pintype "bidirectional"))
      (node (ref "D4") (pin "1") (pinfunction "K_1") (pintype "bidirectional"))
      (node (ref "EPD_C1") (pin "1") (pinfunction "1_1") (pintype "passive"))
      (node (ref "EPD_C10") (pin "1") (pinfunction "1_1") (pintype "passive"))
      (node (ref "EPD_C11") (pin "1") (pinfunction "1_1") (pintype "passive"))
      (node (ref "EPD_C12") (pin "1") (pinfunction "1_1") (pintype "passive"))
      (node (ref "EPD_C2") (pin "1") (pinfunction "1_1") (pintype "passive"))
      (node (ref "EPD_C5") (pin "1") (pinfunction "1_1") (pintype "passive"))
      (node (ref "EPD_C6") (pin "1") (pinfunction "1_1") (pintype "passive"))
      (node (ref "EPD_C7") (pin "1") (pinfunction "1_1") (pintype "passive"))
      (node (ref "EPD_C8") (pin "1") (pinfunction "1_1") (pintype "passive"))
      (node (ref "EPD_C9") (pin "1") (pinfunction "1_1") (pintype "passive"))
      (node (ref "IC1") (pin "D2") (pinfunction "GND_D2") (pintype "bidirectional"))
      (node (ref "IC2") (pin "B1") (pinfunction "IN/TRIG_B1") (pintype "bidirectional"))
      (node (ref "IC2") (pin "B3") (pinfunction "GND_B3") (pintype "bidirectional"))
      (node (ref "IC3") (pin "8") (pinfunction "GNDIO_8") (pintype "bidirectional"))
      (node (ref "IC3") (pin "9") (pinfunction "GND_9") (pintype "bidirectional"))
      (node (ref "IC9") (pin "B1") (pinfunction "VSEL_B1") (pintype "bidirectional"))
      (node (ref "IC9") (pin "C1") (pinfunction "AGND_C1") (pintype "bidirectional"))
      (node (ref "IC9") (pin "C2") (pinfunction "PGND_1_C2") (pintype "bidirectional"))
      (node (ref "IC9") (pin "C3") (pinfunction "PGND_2_C3") (pintype "bidirectional"))
      (node (ref "J1") (pin "17") (pinfunction "17_17") (pintype "bidirectional"))
      (node (ref "J1") (pin "8") (pinfunction "8_8") (pintype "bidirectional"))
      (node (ref "J1") (pin "MP1") (pinfunction "MP1_MP1") (pintype "bidirectional"))
      (node (ref "J1") (pin "MP2") (pinfunction "MP2_MP2") (pintype "bidirectional"))
      (node (ref "J2") (pin "3") (pinfunction "3_3") (pintype "bidirectional"))
      (node (ref "J2") (pin "5") (pinfunction "5_5") (pintype "bidirectional"))
      (node (ref "J4") (pin "A12_B1") (pinfunction "GND_A12_B1") (pintype "power_in"))
      (node (ref "J4") (pin "A1_B12") (pinfunction "GND_A1_B12") (pintype "power_in"))
      (node (ref "J4") (pin "SH1") (pinfunction "SHIELD_SH1") (pintype "passive"))
      (node (ref "J4") (pin "SH2") (pinfunction "SHIELD_SH2") (pintype "passive"))
      (node (ref "J4") (pin "SH3") (pinfunction "SHIELD_SH3") (pintype "passive"))
      (node (ref "J4") (pin "SH4") (pinfunction "SHIELD_SH4") (pintype "passive"))
      (node (ref "R1_USB") (pin "1") (pinfunction "1_1") (pintype "bidirectional"))
      (node (ref "R2_EP_DR") (pin "1") (pinfunction "1_1") (pintype "bidirectional"))
      (node (ref "R2_USB") (pin "2") (pinfunction "2_2") (pintype "bidirectional"))
      (node (ref "R3") (pin "1") (pinfunction "1_1") (pintype "bidirectional"))
      (node (ref "R9") (pin "1") (pinfunction "1_1") (pintype "bidirectional"))
      (node (ref "R_TYPE_SEL") (pin "1") (pinfunction "1_1") (pintype "bidirectional"))
      (node (ref "SJ1") (pin "1") (pinfunction "1_1") (pintype "passive"))
      (node (ref "SW3") (pin "1") (pinfunction "1_1") (pintype "passive"))
      (node (ref "SW_ENT") (pin "1") (pinfunction "1_1") (pintype "passive"))
      (node (ref "SW_UP") (pin "1") (pinfunction "1_1") (pintype "passive"))
      (node (ref "TP_BAT_GND") (pin "TP") (pinfunction "TP_TP") (pintype "input"))
      (node (ref "TP_GND") (pin "TP") (pinfunction "TP_TP") (pintype "input"))
      (node (ref "U1") (pin "P$74") (pinfunction "VSS_PAD_P$74") (pintype "bidirectional"))
      (node (ref "U1") (pin "P$75") (pinfunction "VSS_PAD_P$75") (pintype "bidirectional"))
      (node (ref "U1") (pin "P$76") (pinfunction "VSS_PAD_P$76") (pintype "bidirectional"))
      (node (ref "U1") (pin "P$77") (pinfunction "VSS_PAD_P$77") (pintype "bidirectional"))
      (node (ref "U1") (pin "P$78") (pinfunction "VSS_PAD_P$78") (pintype "bidirectional"))
      (node (ref "U1") (pin "P$79") (pinfunction "VSS_PAD_P$79") (pintype "bidirectional"))
      (node (ref "U1") (pin "P$80") (pinfunction "VSS_PAD_P$80") (pintype "bidirectional"))
      (node (ref "U1") (pin "P$81") (pinfunction "VSS_PAD_P$81") (pintype "bidirectional"))
      (node (ref "U1") (pin "P$82") (pinfunction "VSS_PAD_P$82") (pintype "bidirectional"))
      (node (ref "U1") (pin "P$83") (pinfunction "VSS_PAD_P$83") (pintype "bidirectional"))
      (node (ref "U1") (pin "P$84") (pinfunction "VSS_PAD_P$84") (pintype "bidirectional"))
      (node (ref "U1") (pin "P$85") (pinfunction "VSS_PAD_P$85") (pintype "bidirectional"))
      (node (ref "U1") (pin "P$86") (pinfunction "VSS_PAD_P$86") (pintype "bidirectional"))
      (node (ref "U1") (pin "P$87") (pinfunction "VSS_PAD_P$87") (pintype "bidirectional"))
      (node (ref "U1") (pin "P$88") (pinfunction "VSS_PAD_P$88") (pintype "bidirectional"))
      (node (ref "U1") (pin "P$89") (pinfunction "VSS_PAD_P$89") (pintype "bidirectional"))
      (node (ref "U1") (pin "P$90") (pinfunction "VSS_PAD_P$90") (pintype "bidirectional"))
      (node (ref "U1") (pin "P$B7") (pinfunction "VSS_P$B7") (pintype "power_in"))
      (node (ref "U1") (pin "P$F23") (pinfunction "VSS_PA_P$F23") (pintype "bidirectional"))
      (node (ref "U3") (pin "1") (pinfunction "CTG_1") (pintype "power_in"))
      (node (ref "U3") (pin "4") (pinfunction "GND_4") (pintype "power_in"))
      (node (ref "U3") (pin "6") (pinfunction "QSTRT_6") (pintype "input"))
      (node (ref "U3") (pin "9") (pinfunction "EP_9") (pintype "power_in"))
      (node (ref "X1") (pin "2") (pinfunction "2_2") (pintype "passive"))
      (node (ref "X1") (pin "4") (pinfunction "4_4") (pintype "passive"))
    )
    (net (code "17") (name "HAPTIC_EN") (class "Default")
      (node (ref "IC2") (pin "A1") (pinfunction "EN_A1") (pintype "bidirectional"))
      (node (ref "U1") (pin "P$U1") (pinfunction "P0.12_P$U1") (pintype "bidirectional"))
    )
    (net (code "18") (name "IMU_INT1") (class "Default")
      (node (ref "IC3") (pin "5") (pinfunction "INT1_5") (pintype "bidirectional"))
      (node (ref "U1") (pin "P$N1") (pinfunction "P0.08_P$N1") (pintype "bidirectional"))
    )
    (net (code "19") (name "IMU_INT2") (class "Default")
      (node (ref "IC3") (pin "6") (pinfunction "INT2_6") (pintype "bidirectional"))
      (node (ref "U1") (pin "P$P2") (pinfunction "P1.08_P$P2") (pintype "bidirectional"))
    )
    (net (code "20") (name "LX1") (class "Default")
      (node (ref "IC9") (pin "B2") (pinfunction "SW1_1_B2") (pintype "bidirectional"))
      (node (ref "IC9") (pin "B3") (pinfunction "SW1_2_B3") (pintype "bidirectional"))
      (node (ref "L7") (pin "1") (pinfunction "1_1") (pintype "bidirectional"))
    )
    (net (code "21") (name "LX2") (class "Default")
      (node (ref "IC9") (pin "D2") (pinfunction "SW2_1_D2") (pintype "bidirectional"))
      (node (ref "IC9") (pin "D3") (pinfunction "SW2_2_D3") (pintype "bidirectional"))
      (node (ref "L7") (pin "2") (pinfunction "2_2") (pintype "bidirectional"))
    )
    (net (code "22") (name "MOSI") (class "Default")
      (node (ref "J1") (pin "14") (pinfunction "14_14") (pintype "bidirectional"))
      (node (ref "U1") (pin "P$B13") (pinfunction "P0.03/AIN1_P$B13") (pintype "bidirectional"))
    )
    (net (code "23") (name "Net-(D2-K)") (class "Default")
      (node (ref "C2-EP-DR") (pin "1") (pinfunction "1_1") (pintype "passive"))
      (node (ref "D2") (pin "1") (pinfunction "K_1") (pintype "bidirectional"))
      (node (ref "D4") (pin "2") (pinfunction "A_2") (pintype "bidirectional"))
    )
    (net (code "24") (name "Net-(D5-A)") (class "Default")
      (node (ref "C2-EP-DR") (pin "2") (pinfunction "2_2") (pintype "passive"))
      (node (ref "D5") (pin "2") (pinfunction "A_2") (pintype "bidirectional"))
      (node (ref "L5") (pin "1") (pinfunction "1_1") (pintype "passive"))
      (node (ref "Q3") (pin "3") (pinfunction "D_3") (pintype "bidirectional"))
    )
    (net (code "25") (name "Net-(EPD_C1-Pad2)") (class "Default")
      (node (ref "EPD_C1") (pin "2") (pinfunction "2_2") (pintype "passive"))
      (node (ref "J1") (pin "5") (pinfunction "5_5") (pintype "bidirectional"))
    )
    (net (code "26") (name "Net-(EPD_C2-Pad2)") (class "Default")
      (node (ref "EPD_C2") (pin "2") (pinfunction "2_2") (pintype "passive"))
      (node (ref "J1") (pin "4") (pinfunction "4_4") (pintype "bidirectional"))
    )
    (net (code "27") (name "Net-(EPD_C6-Pad2)") (class "Default")
      (node (ref "EPD_C6") (pin "2") (pinfunction "2_2") (pintype "passive"))
      (node (ref "J1") (pin "18") (pinfunction "18_18") (pintype "bidirectional"))
    )
    (net (code "28") (name "Net-(EPD_C7-Pad2)") (class "Default")
      (node (ref "EPD_C7") (pin "2") (pinfunction "2_2") (pintype "passive"))
      (node (ref "J1") (pin "19") (pinfunction "19_19") (pintype "bidirectional"))
    )
    (net (code "29") (name "Net-(EPD_C8-Pad2)") (class "Default")
      (node (ref "EPD_C8") (pin "2") (pinfunction "2_2") (pintype "passive"))
      (node (ref "J1") (pin "20") (pinfunction "20_20") (pintype "bidirectional"))
    )
    (net (code "30") (name "Net-(EPD_C10-Pad2)") (class "Default")
      (node (ref "EPD_C10") (pin "2") (pinfunction "2_2") (pintype "passive"))
      (node (ref "J1") (pin "22") (pinfunction "22_22") (pintype "bidirectional"))
    )
    (net (code "31") (name "Net-(EPD_C12-Pad2)") (class "Default")
      (node (ref "EPD_C12") (pin "2") (pinfunction "2_2") (pintype "passive"))
      (node (ref "J1") (pin "24") (pinfunction "24_24") (pintype "bidirectional"))
    )
    (net (code "32") (name "Net-(IC1-TS{slash}MR)") (class "Default")
      (node (ref "IC1") (pin "D1") (pinfunction "TS/MR_D1") (pintype "bidirectional"))
      (node (ref "R9") (pin "2") (pinfunction "2_2") (pintype "bidirectional"))
    )
    (net (code "33") (name "Net-(IC2-REG)") (class "Default")
      (node (ref "C32") (pin "2") (pinfunction "2_2") (pintype "passive"))
      (node (ref "IC2") (pin "A2") (pinfunction "REG_A2") (pintype "bidirectional"))
    )
    (net (code "34") (name "Net-(IC3-SDO)") (class "Default")
      (node (ref "IC3") (pin "1") (pinfunction "SDO_1") (pintype "bidirectional"))
      (node (ref "R3") (pin "2") (pinfunction "2_2") (pintype "bidirectional"))
    )
    (net (code "35") (name "Net-(IC9-SCL)") (class "Default")
      (node (ref "IC9") (pin "D1") (pinfunction "SCL_D1") (pintype "bidirectional"))
      (node (ref "R4") (pin "2") (pinfunction "2_2") (pintype "bidirectional"))
    )
    (net (code "36") (name "Net-(IC9-SDA)") (class "Default")
      (node (ref "IC9") (pin "E1") (pinfunction "SDA_E1") (pintype "bidirectional"))
      (node (ref "R2") (pin "2") (pinfunction "2_2") (pintype "bidirectional"))
    )
    (net (code "37") (name "Net-(J4-CC1)") (class "Default")
      (node (ref "J4") (pin "A5") (pinfunction "CC1_A5") (pintype "bidirectional"))
      (node (ref "R1_USB") (pin "2") (pinfunction "2_2") (pintype "bidirectional"))
    )
    (net (code "38") (name "Net-(J4-CC2)") (class "Default")
      (node (ref "J4") (pin "B5") (pinfunction "CC2_B5") (pintype "bidirectional"))
      (node (ref "R2_USB") (pin "1") (pinfunction "1_1") (pintype "bidirectional"))
    )
    (net (code "39") (name "Net-(L2-Pad1)") (class "Default")
      (node (ref "L2") (pin "1") (pinfunction "1_1") (pintype "passive"))
      (node (ref "L3") (pin "2") (pinfunction "2_2") (pintype "passive"))
    )
    (net (code "40") (name "Net-(R1_EP_DR-Pad1)") (class "Default")
      (node (ref "R1_EP_DR") (pin "1") (pinfunction "1_1") (pintype "bidirectional"))
      (node (ref "R_TYPE_SEL") (pin "2") (pinfunction "2_2") (pintype "bidirectional"))
      (node (ref "SJ1") (pin "2") (pinfunction "2_2") (pintype "passive"))
    )
    (net (code "41") (name "Net-(U1-ANT)") (class "Default")
      (node (ref "C3") (pin "1") (pinfunction "1_1") (pintype "passive"))
      (node (ref "L1") (pin "1") (pinfunction "1_1") (pintype "passive"))
      (node (ref "U1") (pin "P$H23") (pinfunction "ANT_P$H23") (pintype "bidirectional"))
    )
    (net (code "42") (name "Net-(U1-DCC)") (class "Default")
      (node (ref "L2") (pin "2") (pinfunction "2_2") (pintype "passive"))
      (node (ref "U1") (pin "P$B3") (pinfunction "DCC_P$B3") (pintype "output"))
    )
    (net (code "43") (name "Net-(U1-DEC2)") (class "Default")
      (node (ref "C13") (pin "1") (pinfunction "1_1") (pintype "passive"))
      (node (ref "U1") (pin "P$A18") (pinfunction "DEC2_P$A18") (pintype "bidirectional"))
    )
    (net (code "44") (name "Net-(U1-DEC3V3)") (class "Default")
      (node (ref "C20") (pin "1") (pinfunction "1_1") (pintype "passive"))
      (node (ref "U1") (pin "P$AC5") (pinfunction "DEC3V3_P$AC5") (pintype "bidirectional"))
    )
    (net (code "45") (name "Net-(U1-DEC5)") (class "Default")
      (node (ref "C9") (pin "1") (pinfunction "1_1") (pintype "passive"))
      (node (ref "U1") (pin "P$N24") (pinfunction "DEC5_P$N24") (pintype "bidirectional"))
    )
    (net (code "46") (name "Net-(U1-XC1)") (class "Default")
      (node (ref "C1") (pin "1") (pinfunction "1_1") (pintype "passive"))
      (node (ref "U1") (pin "P$B24") (pinfunction "XC1_P$B24") (pintype "input"))
      (node (ref "X1") (pin "1") (pinfunction "1_1") (pintype "passive"))
    )
    (net (code "47") (name "Net-(U1-XC2)") (class "Default")
      (node (ref "C2") (pin "1") (pinfunction "1_1") (pintype "passive"))
      (node (ref "U1") (pin "P$A23") (pinfunction "XC2_P$A23") (pintype "output"))
      (node (ref "X1") (pin "3") (pinfunction "3_3") (pintype "passive"))
    )
    (net (code "48") (name "OUT+") (class "Default")
      (node (ref "IC2") (pin "A3") (pinfunction "OUT+_A3") (pintype "bidirectional"))
      (node (ref "TP_OP") (pin "TP") (pinfunction "TP_TP") (pintype "input"))
    )
    (net (code "49") (name "OUT-") (class "Default")
      (node (ref "IC2") (pin "C3") (pinfunction "OUT-_C3") (pintype "bidirectional"))
      (node (ref "TP_ON") (pin "TP") (pinfunction "TP_TP") (pintype "input"))
    )
    (net (code "50") (name "P0.00{slash}XL1") (class "Default")
      (node (ref "C17") (pin "2") (pinfunction "2_2") (pintype "passive"))
      (node (ref "U1") (pin "P$D2") (pinfunction "P0.00/XL1_P$D2") (pintype "bidirectional"))
      (node (ref "X2") (pin "1") (pinfunction "1_1") (pintype "passive"))
    )
    (net (code "51") (name "P0.01{slash}XL2") (class "Default")
      (node (ref "C18") (pin "2") (pinfunction "2_2") (pintype "passive"))
      (node (ref "U1") (pin "P$F2") (pinfunction "P0.01/XL2_P$F2") (pintype "bidirectional"))
      (node (ref "X2") (pin "2") (pinfunction "2_2") (pintype "passive"))
    )
    (net (code "52") (name "P0.13") (class "Default")
      (node (ref "C30") (pin "2") (pinfunction "2_2") (pintype "passive"))
      (node (ref "R5") (pin "1") (pinfunction "1_1") (pintype "bidirectional"))
      (node (ref "SW_UP") (pin "2") (pinfunction "2_2") (pintype "passive"))
      (node (ref "U1") (pin "P$AD8") (pinfunction "P0.13_P$AD8") (pintype "bidirectional"))
    )
    (net (code "53") (name "P0.14") (class "Default")
      (node (ref "C31") (pin "2") (pinfunction "2_2") (pintype "passive"))
      (node (ref "R8") (pin "1") (pinfunction "1_1") (pintype "bidirectional"))
      (node (ref "SW_ENT") (pin "2") (pinfunction "2_2") (pintype "passive"))
      (node (ref "U1") (pin "P$AC9") (pinfunction "P0.14_P$AC9") (pintype "bidirectional"))
    )
    (net (code "54") (name "P1.01") (class "Default")
      (node (ref "Q1") (pin "1") (pinfunction "G_1") (pintype "bidirectional"))
      (node (ref "R_PWR_EPD") (pin "1") (pinfunction "1_1") (pintype "bidirectional"))
      (node (ref "U1") (pin "P$Y23") (pinfunction "P1.01_P$Y23") (pintype "bidirectional"))
    )
    (net (code "55") (name "P1.02") (class "Default")
      (node (ref "C29") (pin "2") (pinfunction "2_2") (pintype "passive"))
      (node (ref "R7") (pin "1") (pinfunction "1_1") (pintype "bidirectional"))
      (node (ref "SW3") (pin "2") (pinfunction "2_2") (pintype "passive"))
      (node (ref "U1") (pin "P$W24") (pinfunction "P1.02_P$W24") (pintype "bidirectional"))
    )
    (net (code "56") (name "PMIC_INT") (class "Default")
      (node (ref "IC1") (pin "A1") (pinfunction "~{INT}_A1") (pintype "bidirectional"))
      (node (ref "U1") (pin "P$T2") (pinfunction "P0.11_P$T2") (pintype "bidirectional"))
    )
    (net (code "57") (name "PREVGH") (class "Default")
      (node (ref "D5") (pin "1") (pinfunction "K_1") (pintype "bidirectional"))
      (node (ref "EPD_C9") (pin "2") (pinfunction "2_2") (pintype "passive"))
      (node (ref "J1") (pin "21") (pinfunction "21_21") (pintype "bidirectional"))
    )
    (net (code "58") (name "PREVGL") (class "Default")
      (node (ref "D2") (pin "2") (pinfunction "A_2") (pintype "bidirectional"))
      (node (ref "EPD_C11") (pin "2") (pinfunction "2_2") (pintype "passive"))
      (node (ref "J1") (pin "23") (pinfunction "23_23") (pintype "bidirectional"))
    )
    (net (code "59") (name "RESE") (class "Default")
      (node (ref "J1") (pin "3") (pinfunction "3_3") (pintype "bidirectional"))
      (node (ref "Q3") (pin "2") (pinfunction "S_2") (pintype "bidirectional"))
      (node (ref "R1_EP_DR") (pin "2") (pinfunction "2_2") (pintype "bidirectional"))
    )
    (net (code "60") (name "RESET") (class "Default")
      (node (ref "J2") (pin "6") (pinfunction "6_6") (pintype "bidirectional"))
      (node (ref "TP_RESET") (pin "TP") (pinfunction "TP_TP") (pintype "input"))
      (node (ref "U1") (pin "P$AC13") (pinfunction "P0.18/RESET_P$AC13") (pintype "bidirectional"))
    )
    (net (code "61") (name "RF") (class "Default")
      (node (ref "ANT1") (pin "1") (pinfunction "FEED_1") (pintype "input"))
      (node (ref "C22") (pin "1") (pinfunction "1_1") (pintype "passive"))
      (node (ref "C4") (pin "1") (pinfunction "1_1") (pintype "passive"))
      (node (ref "L1") (pin "2") (pinfunction "2_2") (pintype "passive"))
    )
    (net (code "62") (name "SCK") (class "Default")
      (node (ref "J1") (pin "13") (pinfunction "13_13") (pintype "bidirectional"))
      (node (ref "U1") (pin "P$A12") (pinfunction "P0.02/AIN0_P$A12") (pintype "bidirectional"))
    )
    (net (code "63") (name "SCL") (class "Default")
      (node (ref "IC1") (pin "B1") (pinfunction "SCL_B1") (pintype "bidirectional"))
      (node (ref "IC2") (pin "C1") (pinfunction "SCL_C1") (pintype "bidirectional"))
      (node (ref "IC3") (pin "12") (pinfunction "SCX_12") (pintype "bidirectional"))
      (node (ref "R17") (pin "2") (pinfunction "2_2") (pintype "bidirectional"))
      (node (ref "R4") (pin "1") (pinfunction "1_1") (pintype "bidirectional"))
      (node (ref "TP_SCL") (pin "TP") (pinfunction "TP_TP") (pintype "input"))
      (node (ref "U1") (pin "P$M2") (pinfunction "P0.07_P$M2") (pintype "bidirectional"))
      (node (ref "U3") (pin "7") (pinfunction "SCL_7") (pintype "input"))
    )
    (net (code "64") (name "SDA") (class "Default")
      (node (ref "IC1") (pin "C1") (pinfunction "SDA_C1") (pintype "bidirectional"))
      (node (ref "IC2") (pin "B2") (pinfunction "SDA_B2") (pintype "bidirectional"))
      (node (ref "IC3") (pin "2") (pinfunction "SDX_2") (pintype "bidirectional"))
      (node (ref "R18") (pin "2") (pinfunction "2_2") (pintype "bidirectional"))
      (node (ref "R2") (pin "1") (pinfunction "1_1") (pintype "bidirectional"))
      (node (ref "TP_SDA") (pin "TP") (pinfunction "TP_TP") (pintype "input"))
      (node (ref "U1") (pin "P$L1") (pinfunction "P0.06_P$L1") (pintype "bidirectional"))
      (node (ref "U3") (pin "8") (pinfunction "SDA_8") (pintype "bidirectional"))
    )
    (net (code "65") (name "SWDCLK") (class "Default")
      (node (ref "J2") (pin "4") (pinfunction "4_4") (pintype "bidirectional"))
      (node (ref "TP_SWDCLK") (pin "TP") (pinfunction "TP_TP") (pintype "input"))
      (node (ref "U1") (pin "P$AA24") (pinfunction "SWDCLK_P$AA24") (pintype "input"))
    )
    (net (code "66") (name "SWDIO") (class "Default")
      (node (ref "J2") (pin "2") (pinfunction "2_2") (pintype "bidirectional"))
      (node (ref "TP_SWDIO") (pin "TP") (pinfunction "TP_TP") (pintype "input"))
      (node (ref "U1") (pin "P$AC24") (pinfunction "SWDIO_P$AC24") (pintype "bidirectional"))
    )
    (net (code "67") (name "SWO") (class "Default")
      (node (ref "TP_SWO") (pin "TP") (pinfunction "TP_TP") (pintype "input"))
      (node (ref "U1") (pin "P$AD22") (pinfunction "P1.00_P$AD22") (pintype "bidirectional"))
    )
    (net (code "68") (name "VBAT") (class "Default")
      (node (ref "C27") (pin "2") (pinfunction "2_2") (pintype "passive"))
      (node (ref "C37") (pin "2") (pinfunction "2_2") (pintype "passive"))
      (node (ref "IC1") (pin "C2") (pinfunction "BAT_C2") (pintype "bidirectional"))
      (node (ref "TP_VBAT") (pin "TP") (pinfunction "TP_TP") (pintype "input"))
      (node (ref "U3") (pin "2") (pinfunction "CELL_2") (pintype "power_in"))
      (node (ref "U3") (pin "3") (pinfunction "VDD_3") (pintype "power_in"))
    )
    (net (code "69") (name "VBUS") (class "Default")
      (node (ref "C21") (pin "1") (pinfunction "1_1") (pintype "passive"))
      (node (ref "C38") (pin "2") (pinfunction "2_2") (pintype "passive"))
      (node (ref "C42") (pin "1") (pinfunction "1_1") (pintype "passive"))
      (node (ref "C43") (pin "1") (pinfunction "1_1") (pintype "passive"))
      (node (ref "D1") (pin "5") (pinfunction "VBUS_5") (pintype "bidirectional"))
      (node (ref "IC1") (pin "A2") (pinfunction "IN_A2") (pintype "bidirectional"))
      (node (ref "J4") (pin "A4_B9") (pinfunction "VBUS_A4_B9") (pintype "power_in"))
      (node (ref "J4") (pin "A9_B4") (pinfunction "VBUS_A9_B4") (pintype "power_in"))
      (node (ref "U1") (pin "P$AD2") (pinfunction "VBUS_P$AD2") (pintype "power_in"))
    )
    (net (code "70") (name "VREG") (class "Default")
      (node (ref "C23") (pin "1") (pinfunction "1_1") (pintype "passive"))
      (node (ref "C24") (pin "2") (pinfunction "2_2") (pintype "passive"))
      (node (ref "C39") (pin "1") (pinfunction "1_1") (pintype "passive"))
      (node (ref "IC1") (pin "B2") (pinfunction "SYS_B2") (pintype "bidirectional"))
      (node (ref "IC9") (pin "A1") (pinfunction "EN_A1") (pintype "bidirectional"))
      (node (ref "IC9") (pin "A2") (pinfunction "VIN_1_A2") (pintype "bidirectional"))
      (node (ref "IC9") (pin "A3") (pinfunction "VIN_2_A3") (pintype "bidirectional"))
      (node (ref "TP_VREG") (pin "TP") (pinfunction "TP_TP") (pintype "input"))
    )
    (net (code "71") (name "unconnected-(ANT1-NC-Pad2)") (class "Default")
      (node (ref "ANT1") (pin "2") (pinfunction "NC_2") (pintype "no_connect"))
    )
    (net (code "72") (name "unconnected-(IC3-ASCL-Pad11)") (class "Default")
      (node (ref "IC3") (pin "11") (pinfunction "ASCL_11") (pintype "bidirectional"))
    )
    (net (code "73") (name "unconnected-(IC3-ASDA-Pad4)") (class "Default")
      (node (ref "IC3") (pin "4") (pinfunction "ASDA_4") (pintype "bidirectional"))
    )
    (net (code "74") (name "unconnected-(J1-Pad1)") (class "Default")
      (node (ref "J1") (pin "1") (pinfunction "1_1") (pintype "bidirectional"))
    )
    (net (code "75") (name "unconnected-(J1-Pad6)") (class "Default")
      (node (ref "J1") (pin "6") (pinfunction "6_6") (pintype "bidirectional"))
    )
    (net (code "76") (name "unconnected-(J1-Pad7)") (class "Default")
      (node (ref "J1") (pin "7") (pinfunction "7_7") (pintype "bidirectional"))
    )
    (net (code "77") (name "unconnected-(J4-SBU1-PadA8)") (class "Default")
      (node (ref "J4") (pin "A8") (pinfunction "SBU1_A8") (pintype "bidirectional"))
    )
    (net (code "78") (name "unconnected-(J4-SBU2-PadB8)") (class "Default")
      (node (ref "J4") (pin "B8") (pinfunction "SBU2_B8") (pintype "bidirectional"))
    )
    (net (code "79") (name "unconnected-(R7-Pad2)") (class "Default")
      (node (ref "R7") (pin "2") (pinfunction "2_2") (pintype "bidirectional"))
    )
    (net (code "80") (name "unconnected-(R8-Pad2)") (class "Default")
      (node (ref "R8") (pin "2") (pinfunction "2_2") (pintype "bidirectional"))
    )
    (net (code "81") (name "unconnected-(U1-DCCH-PadP$AB2)") (class "Default")
      (node (ref "U1") (pin "P$AB2") (pinfunction "DCCH_P$AB2") (pintype "bidirectional"))
    )
    (net (code "82") (name "unconnected-(U1-P0.04{slash}AIN2-PadP$J1)") (class "Default")
      (node (ref "U1") (pin "P$J1") (pinfunction "P0.04/AIN2_P$J1") (pintype "bidirectional"))
    )
    (net (code "83") (name "unconnected-(U1-P0.09{slash}NFC1-PadP$L24)") (class "Default")
      (node (ref "U1") (pin "P$L24") (pinfunction "P0.09/NFC1_P$L24") (pintype "bidirectional"))
    )
    (net (code "84") (name "unconnected-(U1-P0.19-PadP$AC15)") (class "Default")
      (node (ref "U1") (pin "P$AC15") (pinfunction "P0.19_P$AC15") (pintype "bidirectional"))
    )
    (net (code "85") (name "unconnected-(U1-P0.20-PadP$AD16)") (class "Default")
      (node (ref "U1") (pin "P$AD16") (pinfunction "P0.20_P$AD16") (pintype "bidirectional"))
    )
    (net (code "86") (name "unconnected-(U1-P0.21-PadP$AC17)") (class "Default")
      (node (ref "U1") (pin "P$AC17") (pinfunction "P0.21_P$AC17") (pintype "bidirectional"))
    )
    (net (code "87") (name "unconnected-(U1-P0.22-PadP$AD18)") (class "Default")
      (node (ref "U1") (pin "P$AD18") (pinfunction "P0.22_P$AD18") (pintype "bidirectional"))
    )
    (net (code "88") (name "unconnected-(U1-P0.23-PadP$AC19)") (class "Default")
      (node (ref "U1") (pin "P$AC19") (pinfunction "P0.23_P$AC19") (pintype "bidirectional"))
    )
    (net (code "89") (name "unconnected-(U1-P0.24-PadP$AD20)") (class "Default")
      (node (ref "U1") (pin "P$AD20") (pinfunction "P0.24_P$AD20") (pintype "bidirectional"))
    )
    (net (code "90") (name "unconnected-(U1-P0.25-PadP$AC21)") (class "Default")
      (node (ref "U1") (pin "P$AC21") (pinfunction "P0.25_P$AC21") (pintype "bidirectional"))
    )
    (net (code "91") (name "unconnected-(U1-P0.26-PadP$G1)") (class "Default")
      (node (ref "U1") (pin "P$G1") (pinfunction "P0.26_P$G1") (pintype "bidirectional"))
    )
    (net (code "92") (name "unconnected-(U1-P0.27-PadP$H2)") (class "Default")
      (node (ref "U1") (pin "P$H2") (pinfunction "P0.27_P$H2") (pintype "bidirectional"))
    )
    (net (code "93") (name "unconnected-(U1-P0.28{slash}AIN4-PadP$B11)") (class "Default")
      (node (ref "U1") (pin "P$B11") (pinfunction "P0.28/AIN4_P$B11") (pintype "bidirectional"))
    )
    (net (code "94") (name "unconnected-(U1-P0.29{slash}AIN5-PadP$A10)") (class "Default")
      (node (ref "U1") (pin "P$A10") (pinfunction "P0.29/AIN5_P$A10") (pintype "bidirectional"))
    )
    (net (code "95") (name "unconnected-(U1-P0.30{slash}AIN6-PadP$B9)") (class "Default")
      (node (ref "U1") (pin "P$B9") (pinfunction "P0.30/AIN6_P$B9") (pintype "bidirectional"))
    )
    (net (code "96") (name "unconnected-(U1-P0.31{slash}AIN7-PadP$A8)") (class "Default")
      (node (ref "U1") (pin "P$A8") (pinfunction "P0.31/AIN7_P$A8") (pintype "bidirectional"))
    )
    (net (code "97") (name "unconnected-(U1-P1.03-PadP$V23)") (class "Default")
      (node (ref "U1") (pin "P$V23") (pinfunction "P1.03_P$V23") (pintype "bidirectional"))
    )
    (net (code "98") (name "unconnected-(U1-P1.04-PadP$U24)") (class "Default")
      (node (ref "U1") (pin "P$U24") (pinfunction "P1.04_P$U24") (pintype "bidirectional"))
    )
    (net (code "99") (name "unconnected-(U1-P1.05-PadP$T23)") (class "Default")
      (node (ref "U1") (pin "P$T23") (pinfunction "P1.05_P$T23") (pintype "bidirectional"))
    )
    (net (code "100") (name "unconnected-(U1-P1.06-PadP$R24)") (class "Default")
      (node (ref "U1") (pin "P$R24") (pinfunction "P1.06_P$R24") (pintype "bidirectional"))
    )
    (net (code "101") (name "unconnected-(U1-P1.07-PadP$P23)") (class "Default")
      (node (ref "U1") (pin "P$P23") (pinfunction "P1.07_P$P23") (pintype "bidirectional"))
    )
    (net (code "102") (name "unconnected-(U1-P1.09-PadP$R1)") (class "Default")
      (node (ref "U1") (pin "P$R1") (pinfunction "P1.09_P$R1") (pintype "bidirectional"))
    )
    (net (code "103") (name "unconnected-(U1-P1.10-PadP$A20)") (class "Default")
      (node (ref "U1") (pin "P$A20") (pinfunction "P1.10_P$A20") (pintype "bidirectional"))
    )
    (net (code "104") (name "unconnected-(U1-P1.11-PadP$B19)") (class "Default")
      (node (ref "U1") (pin "P$B19") (pinfunction "P1.11_P$B19") (pintype "bidirectional"))
    )
    (net (code "105") (name "unconnected-(U1-P1.12-PadP$B17)") (class "Default")
      (node (ref "U1") (pin "P$B17") (pinfunction "P1.12_P$B17") (pintype "bidirectional"))
    )
    (net (code "106") (name "unconnected-(U1-P1.13-PadP$A16)") (class "Default")
      (node (ref "U1") (pin "P$A16") (pinfunction "P1.13_P$A16") (pintype "bidirectional"))
    )
    (net (code "107") (name "unconnected-(U1-P1.14-PadP$B15)") (class "Default")
      (node (ref "U1") (pin "P$B15") (pinfunction "P1.14_P$B15") (pintype "bidirectional"))
    )
    (net (code "108") (name "unconnected-(U1-P1.15-PadP$A14)") (class "Default")
      (node (ref "U1") (pin "P$A14") (pinfunction "P1.15_P$A14") (pintype "bidirectional"))
    )
  )
)
